# Controller.net
KiCad netlist of a schematic drawn in Altium Designer
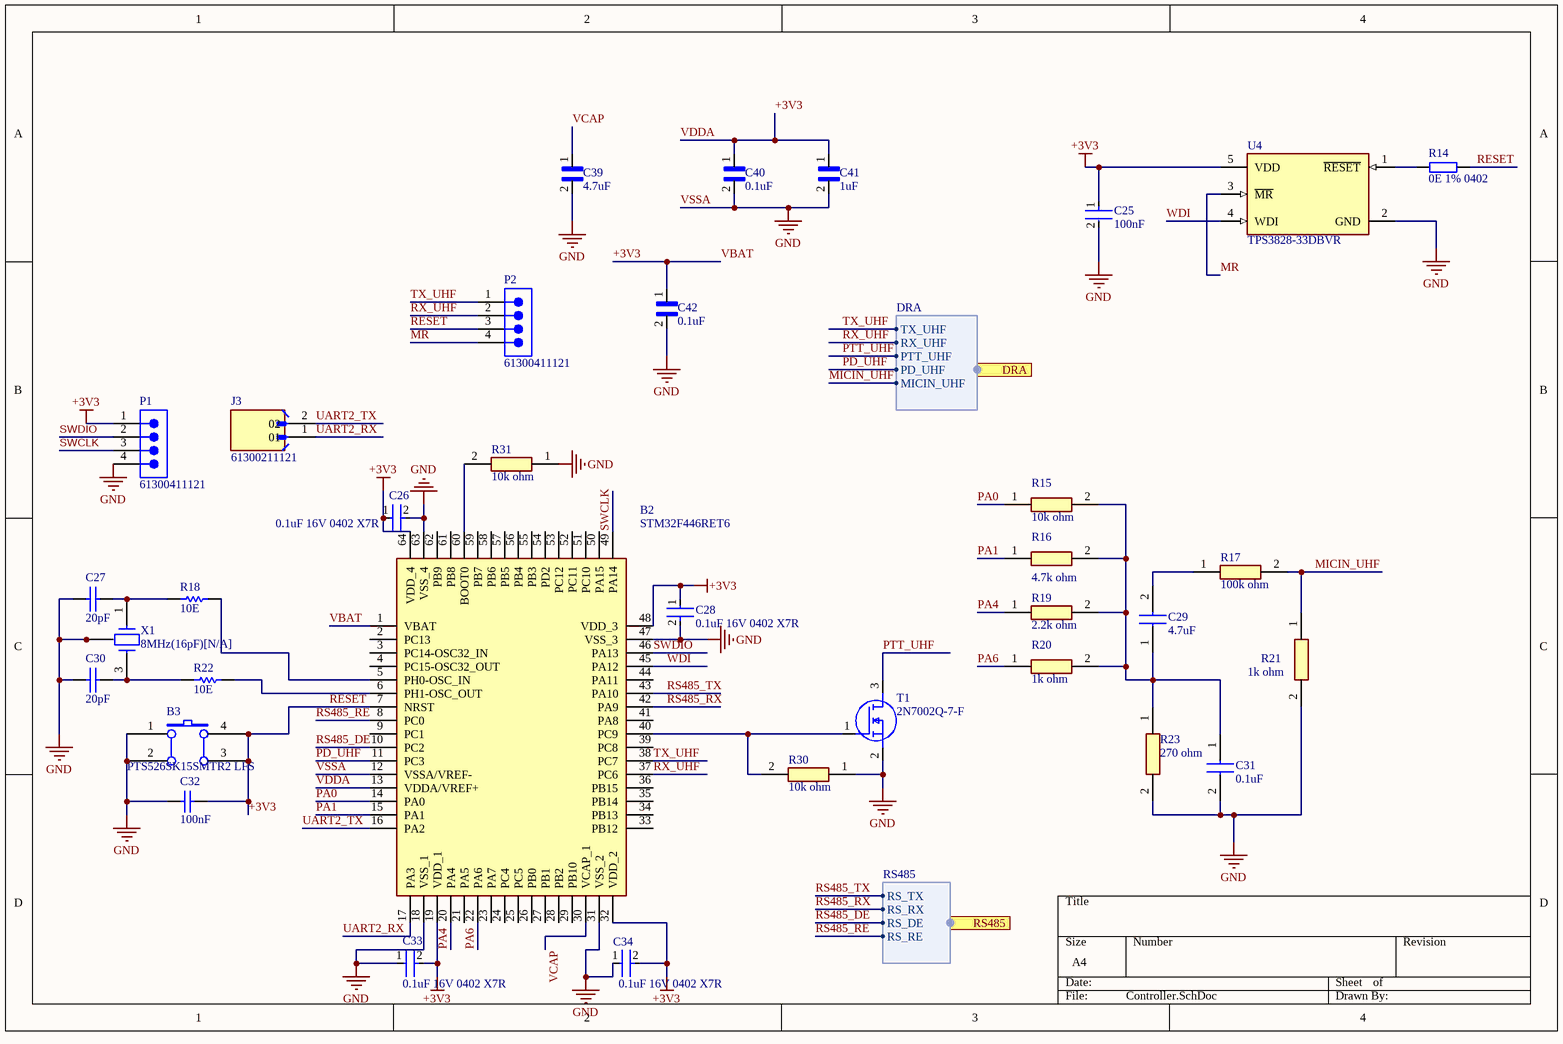
[diagram p0: Controller.SchDoc]

(export (version "E")
  (design (tool "Eeschema 10.0.6"))
  (components
    (comp (ref "B2")
      (value "STM32F446RET6")
      (footprint "LQFP64")
      (fields (field (name "MOUSER PART NUMBER") "511-STM32F446RET6"))
      (libsource (lib "STM32F446RET6") (part "STM32F446RET6"))
    )
    (comp (ref "B3")
      (value "PTS526SK15SMTR2 LFS")
      (footprint "PTS526SK15SMTR2 LFS")
      (description "SE PUSHBUTTON")
      (libsource (lib "TMTC_Board") (part "SW PUSHBUTTON"))
    )
    (comp (ref "C25")
      (value "100nF")
      (footprint "CAP0402S")
      (description "CAP CER 0.1UF 10V X5R 0402")
      (fields (field (name "MANUFACTURER") "Kemet") (field (name "TOLERANCE") "0.1"))
      (libsource (lib "Miscellaneous Devices") (part "b4654b650e69147ec39a6b967a45e02"))
    )
    (comp (ref "C26")
      (value "0.1uF 16V 0402 X7R")
      (footprint "CAP0402S")
      (description "CAP CER 0.1UF 16V X7R 0402")
      (fields (field (name "MANUFACTURER PART NUMBER") "GRM155R71C104KA88D") (field (name "TOLERANCE") "10%"))
      (libsource (lib "Miscellaneous Devices") (part "236180d848d6139a670b325ea6854c9"))
    )
    (comp (ref "C27")
      (value "20pF")
      (footprint "C0201")
      (description "Capacitor")
      (libsource (lib "*") (part "CAP"))
    )
    (comp (ref "C28")
      (value "0.1uF 16V 0402 X7R")
      (footprint "CAP0402S")
      (description "CAP CER 0.1UF 16V X7R 0402")
      (fields (field (name "MANUFACTURER PART NUMBER") "GRM155R71C104KA88D") (field (name "TOLERANCE") "10%"))
      (libsource (lib "Miscellaneous Devices") (part "236180d848d6139a670b325ea6854c9"))
    )
    (comp (ref "C29")
      (value "4.7uF")
      (footprint "CAP0603S")
      (description "Capacitor")
      (fields
        (field (name "MANUFACTURER_PART_NUMBER") "GRM188R61E475KE11D")
        (field (name "MOUSER PART NUMBER") "81-GRM188R61E475KE1D")
      )
      (libsource (lib "*") (part "GRM188R61E475KE11D"))
    )
    (comp (ref "C30")
      (value "20pF")
      (footprint "C0201")
      (description "Capacitor")
      (libsource (lib "*") (part "CAP"))
    )
    (comp (ref "C31")
      (value "0.1uF")
      (footprint "CAP0603S")
      (description "Capacitor")
      (fields
        (field (name "MANUFACTURER_PART_NUMBER") "C0603C104J5RACAUTO")
        (field (name "MOUSER PART NUMBER") "80-C0603C104J5RAUTO")
      )
      (libsource (lib "*") (part "C0603C104J5RACAUTO"))
    )
    (comp (ref "C32")
      (value "100nF")
      (footprint "CAP0603S")
      (description "Capacitor")
      (fields (field (name "PUBLISHER") "Altium Limited"))
      (libsource (lib "Miscellaneous Devices") (part "CAP"))
    )
    (comp (ref "C33")
      (value "0.1uF 16V 0402 X7R")
      (footprint "CAP0402S")
      (description "CAP CER 0.1UF 16V X7R 0402")
      (fields (field (name "MANUFACTURER PART NUMBER") "GRM155R71C104KA88D") (field (name "TOLERANCE") "10%"))
      (libsource (lib "Miscellaneous Devices") (part "236180d848d6139a670b325ea6854c9"))
    )
    (comp (ref "C34")
      (value "0.1uF 16V 0402 X7R")
      (footprint "CAP0402S")
      (description "CAP CER 0.1UF 16V X7R 0402")
      (fields (field (name "MANUFACTURER PART NUMBER") "GRM155R71C104KA88D") (field (name "TOLERANCE") "10%"))
      (libsource (lib "Miscellaneous Devices") (part "236180d848d6139a670b325ea6854c9"))
    )
    (comp (ref "C39")
      (value "4.7uF")
      (footprint "CAP0603S")
      (description "100pF Â±5% 50V Ceramic Capacitor C0G, NP0 0603 _1608 Metric_")
      (fields (field (name "MP") "C0603C101J5GACTU") (field (name "MF") "KEMET"))
      (libsource (lib "C0603C101J5GACTU") (part "C0603C101J5GACTU"))
    )
    (comp (ref "C40")
      (value "0.1uF")
      (footprint "CAP0603S")
      (description "100pF Â±5% 50V Ceramic Capacitor C0G, NP0 0603 _1608 Metric_")
      (fields (field (name "MP") "C0603C101J5GACTU") (field (name "MF") "KEMET"))
      (libsource (lib "C0603C101J5GACTU") (part "C0603C101J5GACTU"))
    )
    (comp (ref "C41")
      (value "1uF")
      (footprint "CAP0603S")
      (description "100pF Â±5% 50V Ceramic Capacitor C0G, NP0 0603 _1608 Metric_")
      (fields (field (name "MP") "C0603C101J5GACTU") (field (name "MF") "KEMET"))
      (libsource (lib "C0603C101J5GACTU") (part "C0603C101J5GACTU"))
    )
    (comp (ref "C42")
      (value "0.1uF")
      (footprint "CAP0603S")
      (description "100pF Â±5% 50V Ceramic Capacitor C0G, NP0 0603 _1608 Metric_")
      (fields (field (name "MP") "C0603C101J5GACTU") (field (name "MF") "KEMET"))
      (libsource (lib "C0603C101J5GACTU") (part "C0603C101J5GACTU"))
    )
    (comp (ref "J3")
      (value "61300211121")
      (footprint "HDR_P2.54_2X1_VERTICAL_TH")
      (description "2 pins, 1 row, straight, gold plating")
      (fields (field (name "MF") "Wurth Electronics"))
      (libsource (lib "61300211121") (part "61300211121"))
    )
    (comp (ref "P1")
      (value "61300411121")
      (footprint "HDR_P2.0_4X1_VERTICAL_TH")
      (libsource (lib "TMTC_Board") (part "CMP-1502-01064-3"))
    )
    (comp (ref "P2")
      (value "61300411121")
      (footprint "HDR_P2.0_4X1_VERTICAL_TH")
      (libsource (lib "TMTC_Board") (part "CMP-1502-01064-3"))
    )
    (comp (ref "R14")
      (value "0E 1% 0402")
      (footprint "RES0402S")
      (description "Resistor SMD 0402")
      (libsource (lib "Schematic-Lib-PhilsLab") (part "RES_0402"))
    )
    (comp (ref "R15")
      (value "10k ohm")
      (footprint "RES0603S")
      (description "Resistor")
      (fields
        (field (name "MANUFACTURER_PART_NUMBER") "CRCW060310K0FKEA")
        (field (name "MOUSER PART NUMBER") "71-CRCW0603-10K-E3")
      )
      (libsource (lib "*") (part "CRCW060310K0FKEA"))
    )
    (comp (ref "R16")
      (value "4.7k ohm")
      (footprint "RES0603S")
      (description "Resistor")
      (fields
        (field (name "MANUFACTURER_PART_NUMBER") "CRCW06034K70FKEA")
        (field (name "MOUSER PART NUMBER") "71-CRCW0603-4.7K-E3")
      )
      (libsource (lib "*") (part "CRCW06034K70FKEA"))
    )
    (comp (ref "R17")
      (value "100k ohm")
      (footprint "RES0603S")
      (description "Resistor")
      (fields
        (field (name "MANUFACTURER_PART_NUMBER") "CRCW0603100KFKEA")
        (field (name "MOUSER PART NUMBER") "71-CRCW0603-100K-E3")
      )
      (libsource (lib "*") (part "CRCW0603100KFKEA"))
    )
    (comp (ref "R18")
      (value "10E")
      (footprint "RES0603S")
      (description "Resistor")
      (fields (field (name "PUBLISHER") "Altium Limited"))
      (libsource (lib "Miscellaneous Devices") (part "Res1"))
    )
    (comp (ref "R19")
      (value "2.2k ohm")
      (footprint "RES0603S")
      (description "Resistor")
      (fields
        (field (name "MANUFACTURER_PART_NUMBER") "CRCW06032K20JNEAHP")
        (field (name "MOUSER PART NUMBER") "71-CRCW06032K20JNEAH")
      )
      (libsource (lib "*") (part "CRCW06032K20JNEAHP"))
    )
    (comp (ref "R20")
      (value "1k ohm")
      (footprint "RES0603S")
      (description "Resistor")
      (fields
        (field (name "MANUFACTURER_PART_NUMBER") "CRCW06031K00FKEAHP")
        (field (name "MOUSER PART NUMBER") "71-CRCW06031K00FKEAH")
      )
      (libsource (lib "*") (part "CRCW06031K00FKEAHP"))
    )
    (comp (ref "R21")
      (value "1k ohm")
      (footprint "RES0603S")
      (description "Resistor")
      (fields
        (field (name "MANUFACTURER_PART_NUMBER") "CRCW06031K00FKEAHP")
        (field (name "MOUSER PART NUMBER") "71-CRCW06031K00FKEAH")
      )
      (libsource (lib "") (part "CRCW06031K00FKEAHP_1"))
    )
    (comp (ref "R22")
      (value "10E")
      (footprint "RES0603S")
      (description "Resistor")
      (fields (field (name "PUBLISHER") "Altium Limited"))
      (libsource (lib "Miscellaneous Devices") (part "Res1"))
    )
    (comp (ref "R23")
      (value "270 ohm")
      (footprint "RES0603S")
      (description "Resistor")
      (fields
        (field (name "MANUFACTURER_PART_NUMBER") "CRCW0603270RFKEA")
        (field (name "MOUSER PART NUMBER") "71-CRCW0603-270-E3")
      )
      (libsource (lib "*") (part "CRCW0603270RFKEA"))
    )
    (comp (ref "R30")
      (value "10k ohm")
      (footprint "RES0603S")
      (description "Resistor")
      (fields
        (field (name "MANUFACTURER_PART_NUMBER") "CRCW060310K0FKEA")
        (field (name "MOUSER PART NUMBER") "71-CRCW0603-10K-E3")
      )
      (libsource (lib "") (part "CRCW060310K0FKEA_1"))
    )
    (comp (ref "R31")
      (value "10k ohm")
      (footprint "RES0603S")
      (description "Resistor")
      (fields
        (field (name "MANUFACTURER_PART_NUMBER") "CRCW060310K0FKEA")
        (field (name "MOUSER PART NUMBER") "71-CRCW0603-10K-E3")
      )
      (libsource (lib "") (part "CRCW060310K0FKEA_1"))
    )
    (comp (ref "T1")
      (value "2N7002Q-7-F")
      (footprint "SOT23_3")
      (description "MOSFET (N-Channel)")
      (fields
        (field (name "MANUFACTURER_PART_NUMBER") "2N7000-G")
        (field (name "MOUSER PART NUMBER") "689-2N7000-G")
      )
      (libsource (lib "*") (part "2N7000-G"))
    )
    (comp (ref "U4")
      (value "TPS3828-33DBVR")
      (footprint "SOT23-5")
      (description "IC 2.93V SUPPLY MONITOR SOT23-5")
      (fields
        (field (name "OCTOPART") "https://octopart.com/tps3828-33dbvt-texas+instruments-505920")
        (field (name "MANUFACTURER PART NUMBER") "TPS3828-33DBVT")
      )
      (libsource (lib "Miscellaneous Devices") (part "340a9547a0ab8213f3a8fa70aee32e0"))
    )
    (comp (ref "X1")
      (value "8MHz(16pF)[N/A]")
      (footprint "WE-XTAL_CFPX-104")
      (description "Crystal")
      (libsource (lib "Miscellaneous Devices") (part "CRYSTAL"))
    )
  )
  (nets
    (net (code "3") (name "+3V3") (class "Default")
      (node (ref "B2") (pin "1") (pinfunction "VBAT_1") (pintype "passive"))
      (node (ref "B2") (pin "13") (pinfunction "VDDA/VREF+_13") (pintype "passive"))
      (node (ref "B2") (pin "19") (pinfunction "VDD_1_19") (pintype "passive"))
      (node (ref "B2") (pin "32") (pinfunction "VDD_2_32") (pintype "passive"))
      (node (ref "B2") (pin "48") (pinfunction "VDD_3_48") (pintype "passive"))
      (node (ref "B2") (pin "64") (pinfunction "VDD_4_64") (pintype "passive"))
      (node (ref "B2") (pin "7") (pinfunction "NRST_7") (pintype "passive"))
      (node (ref "B3") (pin "3") (pinfunction "B1_3") (pintype "passive"))
      (node (ref "B3") (pin "4") (pinfunction "A1_4") (pintype "passive"))
      (node (ref "C25") (pin "1") (pinfunction "1_1") (pintype "passive"))
      (node (ref "C26") (pin "1") (pinfunction "1_1") (pintype "passive"))
      (node (ref "C28") (pin "1") (pinfunction "1_1") (pintype "passive"))
      (node (ref "C32") (pin "1") (pinfunction "1_1") (pintype "passive"))
      (node (ref "C33") (pin "2") (pinfunction "2_2") (pintype "passive"))
      (node (ref "C34") (pin "2") (pinfunction "2_2") (pintype "passive"))
      (node (ref "C40") (pin "1") (pinfunction "1_1") (pintype "passive"))
      (node (ref "C41") (pin "1") (pinfunction "1_1") (pintype "passive"))
      (node (ref "C42") (pin "1") (pinfunction "1_1") (pintype "passive"))
      (node (ref "P1") (pin "1") (pinfunction "1_1") (pintype "passive"))
      (node (ref "P2") (pin "3") (pinfunction "3_3") (pintype "passive"))
      (node (ref "R14") (pin "2") (pinfunction "2_2") (pintype "passive"))
      (node (ref "U4") (pin "5") (pinfunction "VDD_5") (pintype "power_in"))
    )
    (net (code "4") (name "/MICIN_UHF") (class "Default")
      (node (ref "R17") (pin "2") (pinfunction "2_2") (pintype "passive"))
      (node (ref "R21") (pin "1") (pinfunction "1_1") (pintype "passive"))
    )
    (net (code "5") (name "/MR") (class "Default")
      (node (ref "P2") (pin "4") (pinfunction "4_4") (pintype "passive"))
      (node (ref "U4") (pin "3") (pinfunction "~{MR}_3") (pintype "input"))
    )
    (net (code "6") (name "/PA0") (class "Default")
      (node (ref "B2") (pin "14") (pinfunction "PA0_14") (pintype "passive"))
      (node (ref "R15") (pin "1") (pinfunction "1_1") (pintype "passive"))
    )
    (net (code "7") (name "/PA1") (class "Default")
      (node (ref "B2") (pin "15") (pinfunction "PA1_15") (pintype "passive"))
      (node (ref "R16") (pin "1") (pinfunction "1_1") (pintype "passive"))
    )
    (net (code "8") (name "/PA4") (class "Default")
      (node (ref "B2") (pin "20") (pinfunction "PA4_20") (pintype "passive"))
      (node (ref "R19") (pin "1") (pinfunction "1_1") (pintype "passive"))
    )
    (net (code "9") (name "/PA6") (class "Default")
      (node (ref "B2") (pin "22") (pinfunction "PA6_22") (pintype "passive"))
      (node (ref "R20") (pin "1") (pinfunction "1_1") (pintype "passive"))
    )
    (net (code "10") (name "/PD_UHF") (class "Default")
      (node (ref "B2") (pin "11") (pinfunction "PC3_11") (pintype "passive"))
    )
    (net (code "11") (name "/PTT_UHF") (class "Default")
      (node (ref "T1") (pin "3") (pinfunction "D_3") (pintype "passive"))
    )
    (net (code "12") (name "/RS485_DE") (class "Default")
      (node (ref "B2") (pin "10") (pinfunction "PC2_10") (pintype "passive"))
    )
    (net (code "13") (name "/RS485_RE") (class "Default")
      (node (ref "B2") (pin "8") (pinfunction "PC0_8") (pintype "passive"))
    )
    (net (code "14") (name "/RS485_RX") (class "Default")
      (node (ref "B2") (pin "42") (pinfunction "PA9_42") (pintype "passive"))
    )
    (net (code "15") (name "/RS485_TX") (class "Default")
      (node (ref "B2") (pin "43") (pinfunction "PA10_43") (pintype "passive"))
    )
    (net (code "16") (name "/RX_UHF") (class "Default")
      (node (ref "B2") (pin "37") (pinfunction "PC6_37") (pintype "passive"))
      (node (ref "P2") (pin "2") (pinfunction "2_2") (pintype "passive"))
    )
    (net (code "17") (name "/SWCLK") (class "Default")
      (node (ref "B2") (pin "49") (pinfunction "PA14_49") (pintype "passive"))
      (node (ref "P1") (pin "3") (pinfunction "3_3") (pintype "passive"))
    )
    (net (code "18") (name "/SWDIO") (class "Default")
      (node (ref "B2") (pin "46") (pinfunction "PA13_46") (pintype "passive"))
      (node (ref "P1") (pin "2") (pinfunction "2_2") (pintype "passive"))
    )
    (net (code "19") (name "/TX_UHF") (class "Default")
      (node (ref "B2") (pin "38") (pinfunction "PC7_38") (pintype "passive"))
      (node (ref "P2") (pin "1") (pinfunction "1_1") (pintype "passive"))
    )
    (net (code "20") (name "/UART2_RX") (class "Default")
      (node (ref "B2") (pin "17") (pinfunction "PA3_17") (pintype "passive"))
      (node (ref "J3") (pin "1") (pinfunction "01_1") (pintype "passive"))
    )
    (net (code "21") (name "/UART2_TX") (class "Default")
      (node (ref "B2") (pin "16") (pinfunction "PA2_16") (pintype "passive"))
      (node (ref "J3") (pin "2") (pinfunction "02_2") (pintype "passive"))
    )
    (net (code "22") (name "/VCAP") (class "Default")
      (node (ref "B2") (pin "30") (pinfunction "VCAP_1_30") (pintype "passive"))
      (node (ref "C39") (pin "1") (pinfunction "1_1") (pintype "passive"))
    )
    (net (code "23") (name "/WDI") (class "Default")
      (node (ref "B2") (pin "45") (pinfunction "PA12_45") (pintype "passive"))
      (node (ref "U4") (pin "4") (pinfunction "WDI_4") (pintype "input"))
    )
    (net (code "26") (name "GND") (class "Default")
      (node (ref "B2") (pin "12") (pinfunction "VSSA/VREF-_12") (pintype "passive"))
      (node (ref "B2") (pin "18") (pinfunction "VSS_1_18") (pintype "passive"))
      (node (ref "B2") (pin "31") (pinfunction "VSS_2_31") (pintype "passive"))
      (node (ref "B2") (pin "47") (pinfunction "VSS_3_47") (pintype "passive"))
      (node (ref "B2") (pin "63") (pinfunction "VSS_4_63") (pintype "passive"))
      (node (ref "B3") (pin "1") (pinfunction "A0_1") (pintype "passive"))
      (node (ref "B3") (pin "2") (pinfunction "B0_2") (pintype "passive"))
      (node (ref "C25") (pin "2") (pinfunction "2_2") (pintype "passive"))
      (node (ref "C26") (pin "2") (pinfunction "2_2") (pintype "passive"))
      (node (ref "C27") (pin "2") (pinfunction "2_2") (pintype "passive"))
      (node (ref "C28") (pin "2") (pinfunction "2_2") (pintype "passive"))
      (node (ref "C30") (pin "2") (pinfunction "2_2") (pintype "passive"))
      (node (ref "C31") (pin "2") (pinfunction "2_2") (pintype "passive"))
      (node (ref "C32") (pin "2") (pinfunction "2_2") (pintype "passive"))
      (node (ref "C33") (pin "1") (pinfunction "1_1") (pintype "passive"))
      (node (ref "C34") (pin "1") (pinfunction "1_1") (pintype "passive"))
      (node (ref "C39") (pin "2") (pinfunction "2_2") (pintype "passive"))
      (node (ref "C40") (pin "2") (pinfunction "2_2") (pintype "passive"))
      (node (ref "C41") (pin "2") (pinfunction "2_2") (pintype "passive"))
      (node (ref "C42") (pin "2") (pinfunction "2_2") (pintype "passive"))
      (node (ref "P1") (pin "4") (pinfunction "4_4") (pintype "passive"))
      (node (ref "R21") (pin "2") (pinfunction "2_2") (pintype "passive"))
      (node (ref "R23") (pin "2") (pinfunction "2_2") (pintype "passive"))
      (node (ref "R30") (pin "1") (pinfunction "1_1") (pintype "passive"))
      (node (ref "R31") (pin "1") (pinfunction "1_1") (pintype "passive"))
      (node (ref "T1") (pin "2") (pinfunction "S_2") (pintype "passive"))
      (node (ref "U4") (pin "2") (pinfunction "GND_2") (pintype "power_in"))
      (node (ref "X1") (pin "2") (pinfunction "2_2") (pintype "passive"))
      (node (ref "X1") (pin "4") (pinfunction "4_4") (pintype "passive"))
    )
    (net (code "27") (name "Net-(B2-BOOT0)") (class "Default")
      (node (ref "B2") (pin "60") (pinfunction "BOOT0_60") (pintype "passive"))
      (node (ref "R31") (pin "2") (pinfunction "2_2") (pintype "passive"))
    )
    (net (code "28") (name "Net-(B2-PC9)") (class "Default")
      (node (ref "B2") (pin "40") (pinfunction "PC9_40") (pintype "passive"))
      (node (ref "R30") (pin "2") (pinfunction "2_2") (pintype "passive"))
      (node (ref "T1") (pin "1") (pinfunction "G_1") (pintype "passive"))
    )
    (net (code "29") (name "Net-(B2-PH0-OSC_IN)") (class "Default")
      (node (ref "B2") (pin "5") (pinfunction "PH0-OSC_IN_5") (pintype "passive"))
      (node (ref "R18") (pin "1") (pinfunction "1_1") (pintype "passive"))
    )
    (net (code "30") (name "Net-(B2-PH1-OSC_OUT)") (class "Default")
      (node (ref "B2") (pin "6") (pinfunction "PH1-OSC_OUT_6") (pintype "passive"))
      (node (ref "R22") (pin "1") (pinfunction "1_1") (pintype "passive"))
    )
    (net (code "31") (name "Net-(C27-Pad1)") (class "Default")
      (node (ref "C27") (pin "1") (pinfunction "1_1") (pintype "passive"))
      (node (ref "R18") (pin "2") (pinfunction "2_2") (pintype "passive"))
      (node (ref "X1") (pin "1") (pinfunction "1_1") (pintype "passive"))
    )
    (net (code "32") (name "Net-(C29-Pad1)") (class "Default")
      (node (ref "C29") (pin "1") (pinfunction "1_1") (pintype "passive"))
      (node (ref "C31") (pin "1") (pinfunction "1_1") (pintype "passive"))
      (node (ref "R15") (pin "2") (pinfunction "2_2") (pintype "passive"))
      (node (ref "R16") (pin "2") (pinfunction "2_2") (pintype "passive"))
      (node (ref "R19") (pin "2") (pinfunction "2_2") (pintype "passive"))
      (node (ref "R20") (pin "2") (pinfunction "2_2") (pintype "passive"))
      (node (ref "R23") (pin "1") (pinfunction "1_1") (pintype "passive"))
    )
    (net (code "33") (name "Net-(C29-Pad2)") (class "Default")
      (node (ref "C29") (pin "2") (pinfunction "2_2") (pintype "passive"))
      (node (ref "R17") (pin "1") (pinfunction "1_1") (pintype "passive"))
    )
    (net (code "34") (name "Net-(C30-Pad1)") (class "Default")
      (node (ref "C30") (pin "1") (pinfunction "1_1") (pintype "passive"))
      (node (ref "R22") (pin "2") (pinfunction "2_2") (pintype "passive"))
      (node (ref "X1") (pin "3") (pinfunction "3_3") (pintype "passive"))
    )
    (net (code "35") (name "Net-(U4-~{RESET})") (class "Default")
      (node (ref "R14") (pin "1") (pinfunction "1_1") (pintype "passive"))
      (node (ref "U4") (pin "1") (pinfunction "~{RESET}_1") (pintype "input"))
    )
    (net (code "36") (name "unconnected-(B2-PA5-Pad21)") (class "Default")
      (node (ref "B2") (pin "21") (pinfunction "PA5_21") (pintype "passive"))
    )
    (net (code "37") (name "unconnected-(B2-PA7-Pad23)") (class "Default")
      (node (ref "B2") (pin "23") (pinfunction "PA7_23") (pintype "passive"))
    )
    (net (code "38") (name "unconnected-(B2-PA8-Pad41)") (class "Default")
      (node (ref "B2") (pin "41") (pinfunction "PA8_41") (pintype "passive"))
    )
    (net (code "39") (name "unconnected-(B2-PA11-Pad44)") (class "Default")
      (node (ref "B2") (pin "44") (pinfunction "PA11_44") (pintype "passive"))
    )
    (net (code "40") (name "unconnected-(B2-PA15-Pad50)") (class "Default")
      (node (ref "B2") (pin "50") (pinfunction "PA15_50") (pintype "passive"))
    )
    (net (code "41") (name "unconnected-(B2-PB0-Pad26)") (class "Default")
      (node (ref "B2") (pin "26") (pinfunction "PB0_26") (pintype "passive"))
    )
    (net (code "42") (name "unconnected-(B2-PB1-Pad27)") (class "Default")
      (node (ref "B2") (pin "27") (pinfunction "PB1_27") (pintype "passive"))
    )
    (net (code "43") (name "unconnected-(B2-PB2-Pad28)") (class "Default")
      (node (ref "B2") (pin "28") (pinfunction "PB2_28") (pintype "passive"))
    )
    (net (code "44") (name "unconnected-(B2-PB3-Pad55)") (class "Default")
      (node (ref "B2") (pin "55") (pinfunction "PB3_55") (pintype "passive"))
    )
    (net (code "45") (name "unconnected-(B2-PB4-Pad56)") (class "Default")
      (node (ref "B2") (pin "56") (pinfunction "PB4_56") (pintype "passive"))
    )
    (net (code "46") (name "unconnected-(B2-PB5-Pad57)") (class "Default")
      (node (ref "B2") (pin "57") (pinfunction "PB5_57") (pintype "passive"))
    )
    (net (code "47") (name "unconnected-(B2-PB6-Pad58)") (class "Default")
      (node (ref "B2") (pin "58") (pinfunction "PB6_58") (pintype "passive"))
    )
    (net (code "48") (name "unconnected-(B2-PB7-Pad59)") (class "Default")
      (node (ref "B2") (pin "59") (pinfunction "PB7_59") (pintype "passive"))
    )
    (net (code "49") (name "unconnected-(B2-PB8-Pad61)") (class "Default")
      (node (ref "B2") (pin "61") (pinfunction "PB8_61") (pintype "passive"))
    )
    (net (code "50") (name "unconnected-(B2-PB9-Pad62)") (class "Default")
      (node (ref "B2") (pin "62") (pinfunction "PB9_62") (pintype "passive"))
    )
    (net (code "51") (name "unconnected-(B2-PB10-Pad29)") (class "Default")
      (node (ref "B2") (pin "29") (pinfunction "PB10_29") (pintype "passive"))
    )
    (net (code "52") (name "unconnected-(B2-PB12-Pad33)") (class "Default")
      (node (ref "B2") (pin "33") (pinfunction "PB12_33") (pintype "passive"))
    )
    (net (code "53") (name "unconnected-(B2-PB13-Pad34)") (class "Default")
      (node (ref "B2") (pin "34") (pinfunction "PB13_34") (pintype "passive"))
    )
    (net (code "54") (name "unconnected-(B2-PB14-Pad35)") (class "Default")
      (node (ref "B2") (pin "35") (pinfunction "PB14_35") (pintype "passive"))
    )
    (net (code "55") (name "unconnected-(B2-PB15-Pad36)") (class "Default")
      (node (ref "B2") (pin "36") (pinfunction "PB15_36") (pintype "passive"))
    )
    (net (code "56") (name "unconnected-(B2-PC1-Pad9)") (class "Default")
      (node (ref "B2") (pin "9") (pinfunction "PC1_9") (pintype "passive"))
    )
    (net (code "57") (name "unconnected-(B2-PC4-Pad24)") (class "Default")
      (node (ref "B2") (pin "24") (pinfunction "PC4_24") (pintype "passive"))
    )
    (net (code "58") (name "unconnected-(B2-PC5-Pad25)") (class "Default")
      (node (ref "B2") (pin "25") (pinfunction "PC5_25") (pintype "passive"))
    )
    (net (code "59") (name "unconnected-(B2-PC8-Pad39)") (class "Default")
      (node (ref "B2") (pin "39") (pinfunction "PC8_39") (pintype "passive"))
    )
    (net (code "60") (name "unconnected-(B2-PC10-Pad51)") (class "Default")
      (node (ref "B2") (pin "51") (pinfunction "PC10_51") (pintype "passive"))
    )
    (net (code "61") (name "unconnected-(B2-PC11-Pad52)") (class "Default")
      (node (ref "B2") (pin "52") (pinfunction "PC11_52") (pintype "passive"))
    )
    (net (code "62") (name "unconnected-(B2-PC12-Pad53)") (class "Default")
      (node (ref "B2") (pin "53") (pinfunction "PC12_53") (pintype "passive"))
    )
    (net (code "63") (name "unconnected-(B2-PC13-Pad2)") (class "Default")
      (node (ref "B2") (pin "2") (pinfunction "PC13_2") (pintype "passive"))
    )
    (net (code "64") (name "unconnected-(B2-PC14-OSC32_IN-Pad3)") (class "Default")
      (node (ref "B2") (pin "3") (pinfunction "PC14-OSC32_IN_3") (pintype "passive"))
    )
    (net (code "65") (name "unconnected-(B2-PC15-OSC32_OUT-Pad4)") (class "Default")
      (node (ref "B2") (pin "4") (pinfunction "PC15-OSC32_OUT_4") (pintype "passive"))
    )
    (net (code "66") (name "unconnected-(B2-PD2-Pad54)") (class "Default")
      (node (ref "B2") (pin "54") (pinfunction "PD2_54") (pintype "passive"))
    )
  )
)
